# isolated_NO_contacts.net
KiCad netlist of a schematic drawn in Altium Designer
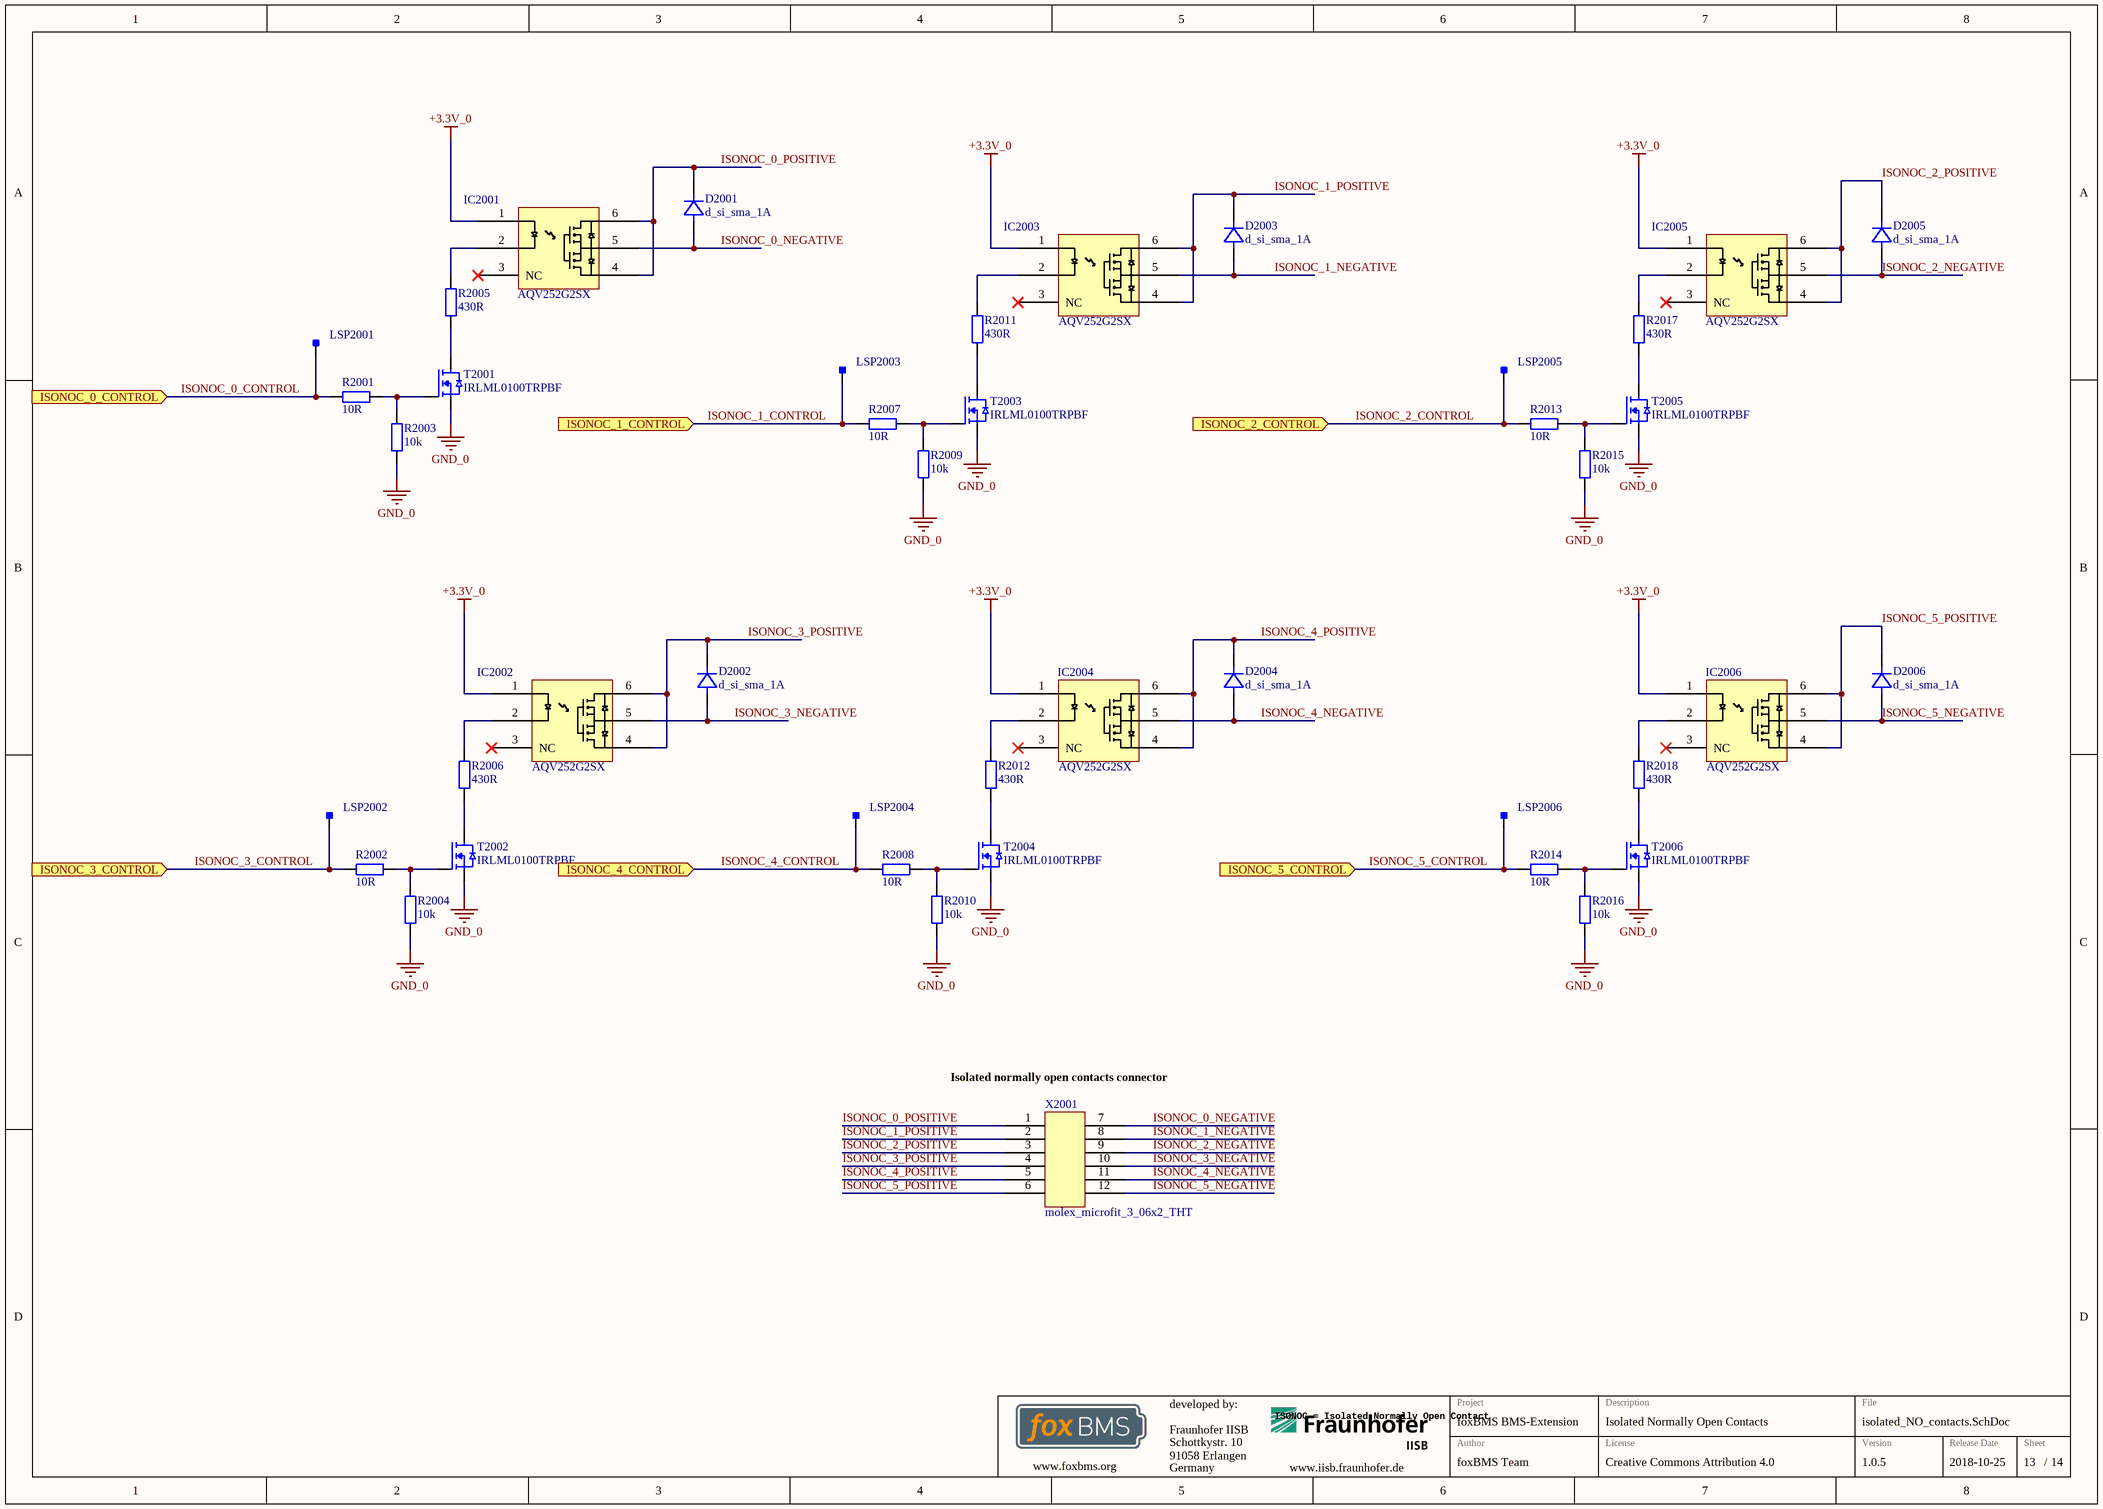
[diagram p0: isolated_NO_contacts.SchDoc]

(export (version "E")
  (design (tool "Eeschema 10.0.6"))
  (components
    (comp (ref "D2001")
      (value "d_si_sma_1A")
      (footprint "DIOM4326X24N")
      (description "Standard Recovery Diode, 100 V, 1 A, Single, 1 V, 2 µs, 30 A")
      (fields (field (name "MANUFACTURER") "ON Semiconductor"))
      (libsource (lib "OE750") (part "D"))
    )
    (comp (ref "D2002")
      (value "d_si_sma_1A")
      (footprint "DIOM4326X24N")
      (description "Standard Recovery Diode, 100 V, 1 A, Single, 1 V, 2 µs, 30 A")
      (fields (field (name "MANUFACTURER") "ON Semiconductor"))
      (libsource (lib "OE750") (part "D"))
    )
    (comp (ref "D2003")
      (value "d_si_sma_1A")
      (footprint "DIOM4326X24N")
      (description "Standard Recovery Diode, 100 V, 1 A, Single, 1 V, 2 µs, 30 A")
      (fields (field (name "MANUFACTURER") "ON Semiconductor"))
      (libsource (lib "OE750") (part "D"))
    )
    (comp (ref "D2004")
      (value "d_si_sma_1A")
      (footprint "DIOM4326X24N")
      (description "Standard Recovery Diode, 100 V, 1 A, Single, 1 V, 2 µs, 30 A")
      (fields (field (name "MANUFACTURER") "ON Semiconductor"))
      (libsource (lib "OE750") (part "D"))
    )
    (comp (ref "D2005")
      (value "d_si_sma_1A")
      (footprint "DIOM4326X24N")
      (description "Standard Recovery Diode, 100 V, 1 A, Single, 1 V, 2 µs, 30 A")
      (fields (field (name "MANUFACTURER") "ON Semiconductor"))
      (libsource (lib "OE750") (part "D"))
    )
    (comp (ref "D2006")
      (value "d_si_sma_1A")
      (footprint "DIOM4326X24N")
      (description "Standard Recovery Diode, 100 V, 1 A, Single, 1 V, 2 µs, 30 A")
      (fields (field (name "MANUFACTURER") "ON Semiconductor"))
      (libsource (lib "OE750") (part "D"))
    )
    (comp (ref "IC2001")
      (value "AQV252G2SX")
      (footprint "SOP254P680X220-6N")
      (description "PhotoMOS Relay")
      (fields (field (name "MANUFACTURER") "Panasonic"))
      (libsource (lib "OE750") (part "AQV252G2SX"))
    )
    (comp (ref "IC2002")
      (value "AQV252G2SX")
      (footprint "SOP254P680X220-6N")
      (description "PhotoMOS Relay")
      (fields (field (name "MANUFACTURER") "Panasonic"))
      (libsource (lib "OE750") (part "AQV252G2SX"))
    )
    (comp (ref "IC2003")
      (value "AQV252G2SX")
      (footprint "SOP254P680X220-6N")
      (description "PhotoMOS Relay")
      (fields (field (name "MANUFACTURER") "Panasonic"))
      (libsource (lib "OE750") (part "AQV252G2SX"))
    )
    (comp (ref "IC2004")
      (value "AQV252G2SX")
      (footprint "SOP254P680X220-6N")
      (description "PhotoMOS Relay")
      (fields (field (name "MANUFACTURER") "Panasonic"))
      (libsource (lib "OE750") (part "AQV252G2SX"))
    )
    (comp (ref "IC2005")
      (value "AQV252G2SX")
      (footprint "SOP254P680X220-6N")
      (description "PhotoMOS Relay")
      (fields (field (name "MANUFACTURER") "Panasonic"))
      (libsource (lib "OE750") (part "AQV252G2SX"))
    )
    (comp (ref "IC2006")
      (value "AQV252G2SX")
      (footprint "SOP254P680X220-6N")
      (description "PhotoMOS Relay")
      (fields (field (name "MANUFACTURER") "Panasonic"))
      (libsource (lib "OE750") (part "AQV252G2SX"))
    )
    (comp (ref "LSP2001")
      (value "Testpoint_Square")
      (footprint "Testpoint_S1")
      (description "Testpoint, square")
      (libsource (lib "OE750") (part "Testpoint_Square"))
    )
    (comp (ref "LSP2002")
      (value "Testpoint_Square")
      (footprint "Testpoint_S1")
      (description "Testpoint, square")
      (libsource (lib "OE750") (part "Testpoint_Square"))
    )
    (comp (ref "LSP2003")
      (value "Testpoint_Square")
      (footprint "Testpoint_S1")
      (description "Testpoint, square")
      (libsource (lib "OE750") (part "Testpoint_Square"))
    )
    (comp (ref "LSP2004")
      (value "Testpoint_Square")
      (footprint "Testpoint_S1")
      (description "Testpoint, square")
      (libsource (lib "OE750") (part "Testpoint_Square"))
    )
    (comp (ref "LSP2005")
      (value "Testpoint_Square")
      (footprint "Testpoint_S1")
      (description "Testpoint, square")
      (libsource (lib "OE750") (part "Testpoint_Square"))
    )
    (comp (ref "LSP2006")
      (value "Testpoint_Square")
      (footprint "Testpoint_S1")
      (description "Testpoint, square")
      (libsource (lib "OE750") (part "Testpoint_Square"))
    )
    (comp (ref "R2001")
      (value "10R")
      (footprint "RESC1608X05N")
      (description "SMD Resistor 10R 0603")
      (fields (field (name "PART NUMBER") "gen_R_10R_0603") (field (name "TOLERANCE") "1%"))
      (libsource (lib "OE750") (part "R"))
    )
    (comp (ref "R2002")
      (value "10R")
      (footprint "RESC1608X05N")
      (description "SMD Resistor 10R 0603")
      (fields (field (name "PART NUMBER") "gen_R_10R_0603") (field (name "TOLERANCE") "1%"))
      (libsource (lib "OE750") (part "R"))
    )
    (comp (ref "R2003")
      (value "10k")
      (footprint "RESC1608X05N")
      (description "SMD Resistor 10k 0603")
      (fields (field (name "PART NUMBER") "gen_R_10k_0603") (field (name "TOLERANCE") "1%"))
      (libsource (lib "OE750") (part "R"))
    )
    (comp (ref "R2004")
      (value "10k")
      (footprint "RESC1608X05N")
      (description "SMD Resistor 10k 0603")
      (fields (field (name "PART NUMBER") "gen_R_10k_0603") (field (name "TOLERANCE") "1%"))
      (libsource (lib "OE750") (part "R"))
    )
    (comp (ref "R2005")
      (value "430R")
      (footprint "RESC1608X05N")
      (description "SMD Resistor 430R 0603")
      (fields (field (name "PART NUMBER") "gen_R_430R_0603") (field (name "TOLERANCE") "1%"))
      (libsource (lib "OE750") (part "R"))
    )
    (comp (ref "R2006")
      (value "430R")
      (footprint "RESC1608X05N")
      (description "SMD Resistor 430R 0603")
      (fields (field (name "PART NUMBER") "gen_R_430R_0603") (field (name "TOLERANCE") "1%"))
      (libsource (lib "OE750") (part "R"))
    )
    (comp (ref "R2007")
      (value "10R")
      (footprint "RESC1608X05N")
      (description "SMD Resistor 10R 0603")
      (fields (field (name "PART NUMBER") "gen_R_10R_0603") (field (name "TOLERANCE") "1%"))
      (libsource (lib "OE750") (part "R"))
    )
    (comp (ref "R2008")
      (value "10R")
      (footprint "RESC1608X05N")
      (description "SMD Resistor 10R 0603")
      (fields (field (name "PART NUMBER") "gen_R_10R_0603") (field (name "TOLERANCE") "1%"))
      (libsource (lib "OE750") (part "R"))
    )
    (comp (ref "R2009")
      (value "10k")
      (footprint "RESC1608X05N")
      (description "SMD Resistor 10k 0603")
      (fields (field (name "PART NUMBER") "gen_R_10k_0603") (field (name "TOLERANCE") "1%"))
      (libsource (lib "OE750") (part "R"))
    )
    (comp (ref "R2010")
      (value "10k")
      (footprint "RESC1608X05N")
      (description "SMD Resistor 10k 0603")
      (fields (field (name "PART NUMBER") "gen_R_10k_0603") (field (name "TOLERANCE") "1%"))
      (libsource (lib "OE750") (part "R"))
    )
    (comp (ref "R2011")
      (value "430R")
      (footprint "RESC1608X05N")
      (description "SMD Resistor 430R 0603")
      (fields (field (name "PART NUMBER") "gen_R_430R_0603") (field (name "TOLERANCE") "1%"))
      (libsource (lib "OE750") (part "R"))
    )
    (comp (ref "R2012")
      (value "430R")
      (footprint "RESC1608X05N")
      (description "SMD Resistor 430R 0603")
      (fields (field (name "PART NUMBER") "gen_R_430R_0603") (field (name "TOLERANCE") "1%"))
      (libsource (lib "OE750") (part "R"))
    )
    (comp (ref "R2013")
      (value "10R")
      (footprint "RESC1608X05N")
      (description "SMD Resistor 10R 0603")
      (fields (field (name "PART NUMBER") "gen_R_10R_0603") (field (name "TOLERANCE") "1%"))
      (libsource (lib "OE750") (part "R"))
    )
    (comp (ref "R2014")
      (value "10R")
      (footprint "RESC1608X05N")
      (description "SMD Resistor 10R 0603")
      (fields (field (name "PART NUMBER") "gen_R_10R_0603") (field (name "TOLERANCE") "1%"))
      (libsource (lib "OE750") (part "R"))
    )
    (comp (ref "R2015")
      (value "10k")
      (footprint "RESC1608X05N")
      (description "SMD Resistor 10k 0603")
      (fields (field (name "PART NUMBER") "gen_R_10k_0603") (field (name "TOLERANCE") "1%"))
      (libsource (lib "OE750") (part "R"))
    )
    (comp (ref "R2016")
      (value "10k")
      (footprint "RESC1608X05N")
      (description "SMD Resistor 10k 0603")
      (fields (field (name "PART NUMBER") "gen_R_10k_0603") (field (name "TOLERANCE") "1%"))
      (libsource (lib "OE750") (part "R"))
    )
    (comp (ref "R2017")
      (value "430R")
      (footprint "RESC1608X05N")
      (description "SMD Resistor 430R 0603")
      (fields (field (name "PART NUMBER") "gen_R_430R_0603") (field (name "TOLERANCE") "1%"))
      (libsource (lib "OE750") (part "R"))
    )
    (comp (ref "R2018")
      (value "430R")
      (footprint "RESC1608X05N")
      (description "SMD Resistor 430R 0603")
      (fields (field (name "PART NUMBER") "gen_R_430R_0603") (field (name "TOLERANCE") "1%"))
      (libsource (lib "OE750") (part "R"))
    )
    (comp (ref "T2001")
      (value "IRLML0100TRPBF")
      (footprint "SOT95P237X110-3N")
      (description "MOSFET-Transistor, n-Kanal, 1.6 A, 100 V, 0.178 ohm, 10 V, 2.5 V")
      (fields (field (name "MANUFACTURER") "Infineon"))
      (libsource (lib "OE750") (part "NMOS"))
    )
    (comp (ref "T2002")
      (value "IRLML0100TRPBF")
      (footprint "SOT95P237X110-3N")
      (description "MOSFET-Transistor, n-Kanal, 1.6 A, 100 V, 0.178 ohm, 10 V, 2.5 V")
      (fields (field (name "MANUFACTURER") "Infineon"))
      (libsource (lib "OE750") (part "NMOS"))
    )
    (comp (ref "T2003")
      (value "IRLML0100TRPBF")
      (footprint "SOT95P237X110-3N")
      (description "MOSFET-Transistor, n-Kanal, 1.6 A, 100 V, 0.178 ohm, 10 V, 2.5 V")
      (fields (field (name "MANUFACTURER") "Infineon"))
      (libsource (lib "OE750") (part "NMOS"))
    )
    (comp (ref "T2004")
      (value "IRLML0100TRPBF")
      (footprint "SOT95P237X110-3N")
      (description "MOSFET-Transistor, n-Kanal, 1.6 A, 100 V, 0.178 ohm, 10 V, 2.5 V")
      (fields (field (name "MANUFACTURER") "Infineon"))
      (libsource (lib "OE750") (part "NMOS"))
    )
    (comp (ref "T2005")
      (value "IRLML0100TRPBF")
      (footprint "SOT95P237X110-3N")
      (description "MOSFET-Transistor, n-Kanal, 1.6 A, 100 V, 0.178 ohm, 10 V, 2.5 V")
      (fields (field (name "MANUFACTURER") "Infineon"))
      (libsource (lib "OE750") (part "NMOS"))
    )
    (comp (ref "T2006")
      (value "IRLML0100TRPBF")
      (footprint "SOT95P237X110-3N")
      (description "MOSFET-Transistor, n-Kanal, 1.6 A, 100 V, 0.178 ohm, 10 V, 2.5 V")
      (fields (field (name "MANUFACTURER") "Infineon"))
      (libsource (lib "OE750") (part "NMOS"))
    )
    (comp (ref "X2001")
      (value "molex_microfit_3_06x2_THT")
      (footprint "MOLEX_MICROFIT_06x2_THT")
      (fields (field (name "MANUFACTURER") "Molex"))
      (libsource (lib "OE750") (part "X6x2"))
    )
  )
  (nets
    (net (code "1") (name "+3.3V_0") (class "Default")
      (node (ref "IC2001") (pin "1") (pintype "passive"))
      (node (ref "IC2002") (pin "1") (pintype "passive"))
      (node (ref "IC2003") (pin "1") (pintype "passive"))
      (node (ref "IC2004") (pin "1") (pintype "passive"))
      (node (ref "IC2005") (pin "1") (pintype "passive"))
      (node (ref "IC2006") (pin "1") (pintype "passive"))
    )
    (net (code "2") (name "/ISONOC_0_CONTROL") (class "Default")
      (node (ref "LSP2001") (pin "1") (pinfunction "1_1") (pintype "passive"))
      (node (ref "R2001") (pin "2") (pinfunction "2_2") (pintype "passive"))
    )
    (net (code "3") (name "/ISONOC_0_NEGATIVE") (class "Default")
      (node (ref "D2001") (pin "2") (pinfunction "A_2") (pintype "passive"))
      (node (ref "IC2001") (pin "5") (pintype "passive"))
      (node (ref "X2001") (pin "7") (pintype "passive"))
    )
    (net (code "4") (name "/ISONOC_0_POSITIVE") (class "Default")
      (node (ref "D2001") (pin "1") (pinfunction "K_1") (pintype "passive"))
      (node (ref "IC2001") (pin "4") (pintype "passive"))
      (node (ref "IC2001") (pin "6") (pintype "passive"))
      (node (ref "X2001") (pin "1") (pintype "passive"))
    )
    (net (code "5") (name "/ISONOC_1_CONTROL") (class "Default")
      (node (ref "LSP2003") (pin "1") (pinfunction "1_1") (pintype "passive"))
      (node (ref "R2007") (pin "2") (pinfunction "2_2") (pintype "passive"))
    )
    (net (code "6") (name "/ISONOC_1_NEGATIVE") (class "Default")
      (node (ref "D2003") (pin "2") (pinfunction "A_2") (pintype "passive"))
      (node (ref "IC2003") (pin "5") (pintype "passive"))
      (node (ref "X2001") (pin "8") (pintype "passive"))
    )
    (net (code "7") (name "/ISONOC_1_POSITIVE") (class "Default")
      (node (ref "D2003") (pin "1") (pinfunction "K_1") (pintype "passive"))
      (node (ref "IC2003") (pin "4") (pintype "passive"))
      (node (ref "IC2003") (pin "6") (pintype "passive"))
      (node (ref "X2001") (pin "2") (pintype "passive"))
    )
    (net (code "8") (name "/ISONOC_2_CONTROL") (class "Default")
      (node (ref "LSP2005") (pin "1") (pinfunction "1_1") (pintype "passive"))
      (node (ref "R2013") (pin "2") (pinfunction "2_2") (pintype "passive"))
    )
    (net (code "9") (name "/ISONOC_2_NEGATIVE") (class "Default")
      (node (ref "D2005") (pin "2") (pinfunction "A_2") (pintype "passive"))
      (node (ref "IC2005") (pin "5") (pintype "passive"))
      (node (ref "X2001") (pin "9") (pintype "passive"))
    )
    (net (code "10") (name "/ISONOC_2_POSITIVE") (class "Default")
      (node (ref "D2005") (pin "1") (pinfunction "K_1") (pintype "passive"))
      (node (ref "IC2005") (pin "4") (pintype "passive"))
      (node (ref "IC2005") (pin "6") (pintype "passive"))
      (node (ref "X2001") (pin "3") (pintype "passive"))
    )
    (net (code "11") (name "/ISONOC_3_CONTROL") (class "Default")
      (node (ref "LSP2002") (pin "1") (pinfunction "1_1") (pintype "passive"))
      (node (ref "R2002") (pin "2") (pinfunction "2_2") (pintype "passive"))
    )
    (net (code "12") (name "/ISONOC_3_NEGATIVE") (class "Default")
      (node (ref "D2002") (pin "2") (pinfunction "A_2") (pintype "passive"))
      (node (ref "IC2002") (pin "5") (pintype "passive"))
      (node (ref "X2001") (pin "10") (pintype "passive"))
    )
    (net (code "13") (name "/ISONOC_3_POSITIVE") (class "Default")
      (node (ref "D2002") (pin "1") (pinfunction "K_1") (pintype "passive"))
      (node (ref "IC2002") (pin "4") (pintype "passive"))
      (node (ref "IC2002") (pin "6") (pintype "passive"))
      (node (ref "X2001") (pin "4") (pintype "passive"))
    )
    (net (code "14") (name "/ISONOC_4_CONTROL") (class "Default")
      (node (ref "LSP2004") (pin "1") (pinfunction "1_1") (pintype "passive"))
      (node (ref "R2008") (pin "2") (pinfunction "2_2") (pintype "passive"))
    )
    (net (code "15") (name "/ISONOC_4_NEGATIVE") (class "Default")
      (node (ref "D2004") (pin "2") (pinfunction "A_2") (pintype "passive"))
      (node (ref "IC2004") (pin "5") (pintype "passive"))
      (node (ref "X2001") (pin "11") (pintype "passive"))
    )
    (net (code "16") (name "/ISONOC_4_POSITIVE") (class "Default")
      (node (ref "D2004") (pin "1") (pinfunction "K_1") (pintype "passive"))
      (node (ref "IC2004") (pin "4") (pintype "passive"))
      (node (ref "IC2004") (pin "6") (pintype "passive"))
      (node (ref "X2001") (pin "5") (pintype "passive"))
    )
    (net (code "17") (name "/ISONOC_5_CONTROL") (class "Default")
      (node (ref "LSP2006") (pin "1") (pinfunction "1_1") (pintype "passive"))
      (node (ref "R2014") (pin "2") (pinfunction "2_2") (pintype "passive"))
    )
    (net (code "18") (name "/ISONOC_5_NEGATIVE") (class "Default")
      (node (ref "D2006") (pin "2") (pinfunction "A_2") (pintype "passive"))
      (node (ref "IC2006") (pin "5") (pintype "passive"))
      (node (ref "X2001") (pin "12") (pintype "passive"))
    )
    (net (code "19") (name "/ISONOC_5_POSITIVE") (class "Default")
      (node (ref "D2006") (pin "1") (pinfunction "K_1") (pintype "passive"))
      (node (ref "IC2006") (pin "4") (pintype "passive"))
      (node (ref "IC2006") (pin "6") (pintype "passive"))
      (node (ref "X2001") (pin "6") (pintype "passive"))
    )
    (net (code "20") (name "GND_0") (class "Default")
      (node (ref "R2003") (pin "1") (pinfunction "1_1") (pintype "passive"))
      (node (ref "R2004") (pin "1") (pinfunction "1_1") (pintype "passive"))
      (node (ref "R2009") (pin "1") (pinfunction "1_1") (pintype "passive"))
      (node (ref "R2010") (pin "1") (pinfunction "1_1") (pintype "passive"))
      (node (ref "R2015") (pin "1") (pinfunction "1_1") (pintype "passive"))
      (node (ref "R2016") (pin "1") (pinfunction "1_1") (pintype "passive"))
      (node (ref "T2001") (pin "S") (pinfunction "S_S") (pintype "passive"))
      (node (ref "T2002") (pin "S") (pinfunction "S_S") (pintype "passive"))
      (node (ref "T2003") (pin "S") (pinfunction "S_S") (pintype "passive"))
      (node (ref "T2004") (pin "S") (pinfunction "S_S") (pintype "passive"))
      (node (ref "T2005") (pin "S") (pinfunction "S_S") (pintype "passive"))
      (node (ref "T2006") (pin "S") (pinfunction "S_S") (pintype "passive"))
    )
    (net (code "21") (name "Net-(IC2001-Pad2)") (class "Default")
      (node (ref "IC2001") (pin "2") (pintype "power_in"))
      (node (ref "R2005") (pin "2") (pinfunction "2_2") (pintype "passive"))
    )
    (net (code "22") (name "Net-(IC2002-Pad2)") (class "Default")
      (node (ref "IC2002") (pin "2") (pintype "power_in"))
      (node (ref "R2006") (pin "2") (pinfunction "2_2") (pintype "passive"))
    )
    (net (code "23") (name "Net-(IC2003-Pad2)") (class "Default")
      (node (ref "IC2003") (pin "2") (pintype "power_in"))
      (node (ref "R2011") (pin "2") (pinfunction "2_2") (pintype "passive"))
    )
    (net (code "24") (name "Net-(IC2004-Pad2)") (class "Default")
      (node (ref "IC2004") (pin "2") (pintype "power_in"))
      (node (ref "R2012") (pin "2") (pinfunction "2_2") (pintype "passive"))
    )
    (net (code "25") (name "Net-(IC2005-Pad2)") (class "Default")
      (node (ref "IC2005") (pin "2") (pintype "power_in"))
      (node (ref "R2017") (pin "2") (pinfunction "2_2") (pintype "passive"))
    )
    (net (code "26") (name "Net-(IC2006-Pad2)") (class "Default")
      (node (ref "IC2006") (pin "2") (pintype "power_in"))
      (node (ref "R2018") (pin "2") (pinfunction "2_2") (pintype "passive"))
    )
    (net (code "27") (name "Net-(R2001-Pad1)") (class "Default")
      (node (ref "R2001") (pin "1") (pinfunction "1_1") (pintype "passive"))
      (node (ref "R2003") (pin "2") (pinfunction "2_2") (pintype "passive"))
      (node (ref "T2001") (pin "G") (pinfunction "G_G") (pintype "passive"))
    )
    (net (code "28") (name "Net-(R2002-Pad1)") (class "Default")
      (node (ref "R2002") (pin "1") (pinfunction "1_1") (pintype "passive"))
      (node (ref "R2004") (pin "2") (pinfunction "2_2") (pintype "passive"))
      (node (ref "T2002") (pin "G") (pinfunction "G_G") (pintype "passive"))
    )
    (net (code "29") (name "Net-(R2005-Pad1)") (class "Default")
      (node (ref "R2005") (pin "1") (pinfunction "1_1") (pintype "passive"))
      (node (ref "T2001") (pin "D") (pinfunction "D_D") (pintype "passive"))
    )
    (net (code "30") (name "Net-(R2006-Pad1)") (class "Default")
      (node (ref "R2006") (pin "1") (pinfunction "1_1") (pintype "passive"))
      (node (ref "T2002") (pin "D") (pinfunction "D_D") (pintype "passive"))
    )
    (net (code "31") (name "Net-(R2007-Pad1)") (class "Default")
      (node (ref "R2007") (pin "1") (pinfunction "1_1") (pintype "passive"))
      (node (ref "R2009") (pin "2") (pinfunction "2_2") (pintype "passive"))
      (node (ref "T2003") (pin "G") (pinfunction "G_G") (pintype "passive"))
    )
    (net (code "32") (name "Net-(R2008-Pad1)") (class "Default")
      (node (ref "R2008") (pin "1") (pinfunction "1_1") (pintype "passive"))
      (node (ref "R2010") (pin "2") (pinfunction "2_2") (pintype "passive"))
      (node (ref "T2004") (pin "G") (pinfunction "G_G") (pintype "passive"))
    )
    (net (code "33") (name "Net-(R2011-Pad1)") (class "Default")
      (node (ref "R2011") (pin "1") (pinfunction "1_1") (pintype "passive"))
      (node (ref "T2003") (pin "D") (pinfunction "D_D") (pintype "passive"))
    )
    (net (code "34") (name "Net-(R2012-Pad1)") (class "Default")
      (node (ref "R2012") (pin "1") (pinfunction "1_1") (pintype "passive"))
      (node (ref "T2004") (pin "D") (pinfunction "D_D") (pintype "passive"))
    )
    (net (code "35") (name "Net-(R2013-Pad1)") (class "Default")
      (node (ref "R2013") (pin "1") (pinfunction "1_1") (pintype "passive"))
      (node (ref "R2015") (pin "2") (pinfunction "2_2") (pintype "passive"))
      (node (ref "T2005") (pin "G") (pinfunction "G_G") (pintype "passive"))
    )
    (net (code "36") (name "Net-(R2014-Pad1)") (class "Default")
      (node (ref "R2014") (pin "1") (pinfunction "1_1") (pintype "passive"))
      (node (ref "R2016") (pin "2") (pinfunction "2_2") (pintype "passive"))
      (node (ref "T2006") (pin "G") (pinfunction "G_G") (pintype "passive"))
    )
    (net (code "37") (name "Net-(R2017-Pad1)") (class "Default")
      (node (ref "R2017") (pin "1") (pinfunction "1_1") (pintype "passive"))
      (node (ref "T2005") (pin "D") (pinfunction "D_D") (pintype "passive"))
    )
    (net (code "38") (name "Net-(R2018-Pad1)") (class "Default")
      (node (ref "R2018") (pin "1") (pinfunction "1_1") (pintype "passive"))
      (node (ref "T2006") (pin "D") (pinfunction "D_D") (pintype "passive"))
    )
    (net (code "39") (name "unconnected-(IC2001-NC-Pad3)") (class "Default")
      (node (ref "IC2001") (pin "3") (pinfunction "NC_3") (pintype "passive+no_connect"))
    )
    (net (code "40") (name "unconnected-(IC2002-NC-Pad3)") (class "Default")
      (node (ref "IC2002") (pin "3") (pinfunction "NC_3") (pintype "passive+no_connect"))
    )
    (net (code "41") (name "unconnected-(IC2003-NC-Pad3)") (class "Default")
      (node (ref "IC2003") (pin "3") (pinfunction "NC_3") (pintype "passive+no_connect"))
    )
    (net (code "42") (name "unconnected-(IC2004-NC-Pad3)") (class "Default")
      (node (ref "IC2004") (pin "3") (pinfunction "NC_3") (pintype "passive+no_connect"))
    )
    (net (code "43") (name "unconnected-(IC2005-NC-Pad3)") (class "Default")
      (node (ref "IC2005") (pin "3") (pinfunction "NC_3") (pintype "passive+no_connect"))
    )
    (net (code "44") (name "unconnected-(IC2006-NC-Pad3)") (class "Default")
      (node (ref "IC2006") (pin "3") (pinfunction "NC_3") (pintype "passive+no_connect"))
    )
  )
)
